# mptt-controller.net
KiCad netlist of a schematic drawn in EAGLE
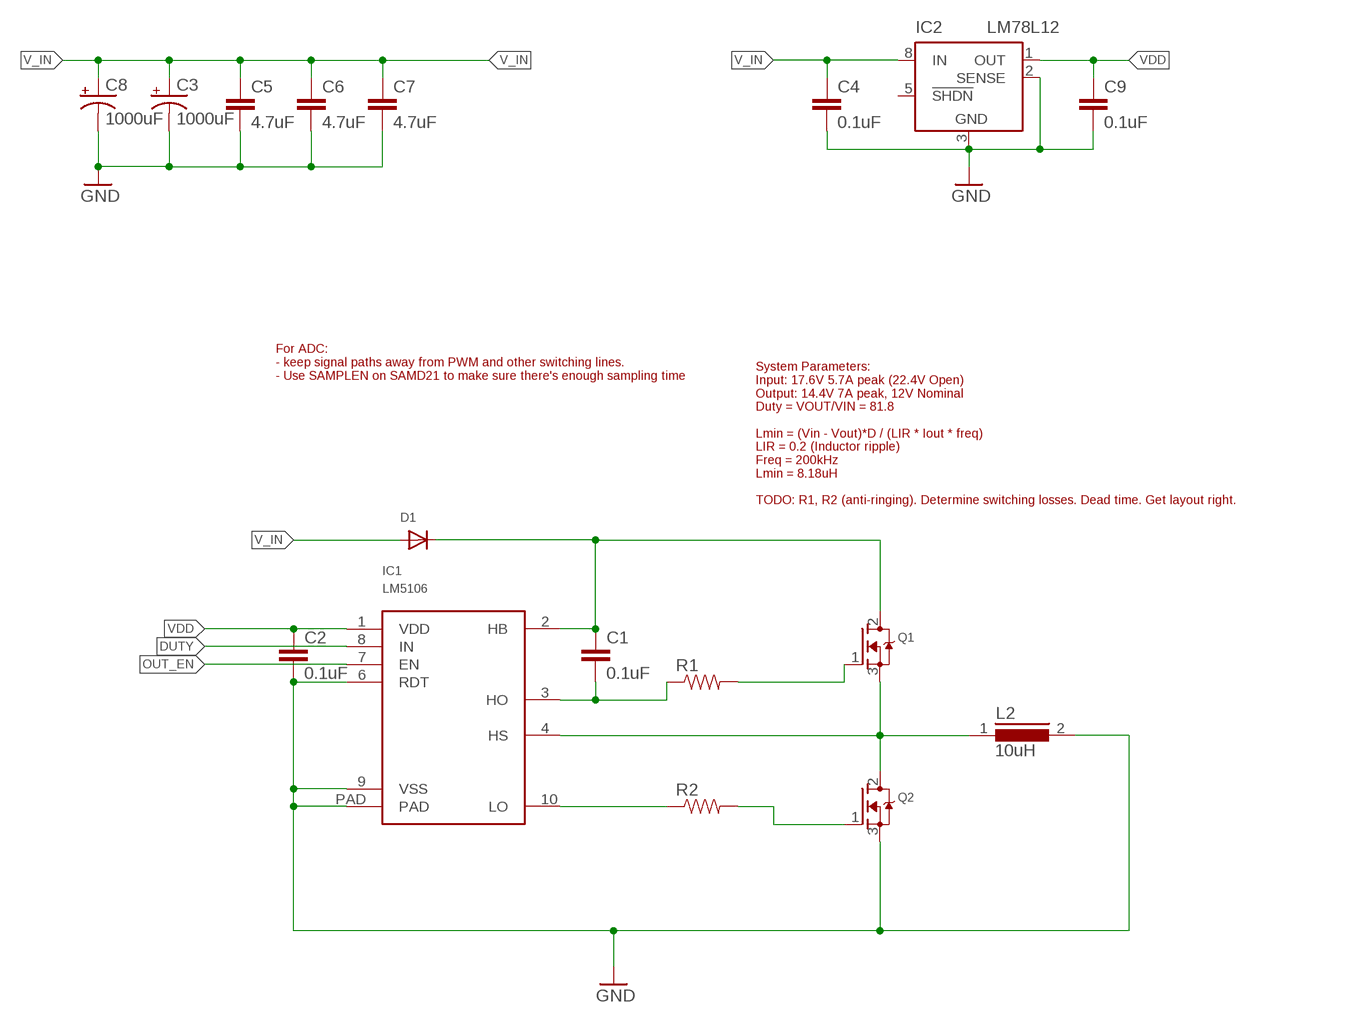
[diagram p0: schematic, sheet 1]

(export (version "E")
  (design (tool "Eeschema 10.0.6"))
  (components
    (comp (ref "C1")
      (value "0.1uF")
      (footprint "eagle-import:0603-CAP")
      (libsource (lib "eagle-import") (part "0.1UF-25V(+80/-20%)(0603)"))
    )
    (comp (ref "C2")
      (value "0.1uF")
      (footprint "eagle-import:0603-CAP")
      (libsource (lib "eagle-import") (part "0.1UF-25V(+80/-20%)(0603)"))
    )
    (comp (ref "C3")
      (value "1000uF")
      (footprint "eagle-import:CPOL-RADIAL-1000UF-25V")
      (libsource (lib "eagle-import") (part "CAP_POLPTH4"))
    )
    (comp (ref "C4")
      (value "0.1uF")
      (footprint "eagle-import:0603-CAP")
      (libsource (lib "eagle-import") (part "0.1UF-25V(+80/-20%)(0603)"))
    )
    (comp (ref "C5")
      (value "4.7uF")
      (footprint "eagle-import:0603-CAP")
      (libsource (lib "eagle-import") (part "0.1UF-25V(+80/-20%)(0603)"))
    )
    (comp (ref "C6")
      (value "4.7uF")
      (footprint "eagle-import:0603-CAP")
      (libsource (lib "eagle-import") (part "0.1UF-25V(+80/-20%)(0603)"))
    )
    (comp (ref "C7")
      (value "4.7uF")
      (footprint "eagle-import:0603-CAP")
      (libsource (lib "eagle-import") (part "0.1UF-25V(+80/-20%)(0603)"))
    )
    (comp (ref "C8")
      (value "1000uF")
      (footprint "eagle-import:CPOL-RADIAL-1000UF-25V")
      (libsource (lib "eagle-import") (part "CAP_POLPTH4"))
    )
    (comp (ref "C9")
      (value "0.1uF")
      (footprint "eagle-import:0603-CAP")
      (libsource (lib "eagle-import") (part "0.1UF-25V(+80/-20%)(0603)"))
    )
    (comp (ref "D1")
      (value "DIODE_SOD-123FL")
      (footprint "eagle-import:SOD-123FL")
      (libsource (lib "eagle-import") (part "DIODE_SOD-123FL"))
    )
    (comp (ref "IC1")
      (value "LM5106")
      (footprint "eagle-import:10WSON")
      (libsource (lib "eagle-import") (part "LM5106"))
    )
    (comp (ref "IC2")
      (value "LM78L12")
      (footprint "eagle-import:SOIC8")
      (fields (field (name "MPN") "LT1963ES8"))
      (libsource (lib "eagle-import") (part "LT1963ES8"))
    )
    (comp (ref "L2")
      (value "10uH")
      (footprint "eagle-import:SFT1040")
      (libsource (lib "eagle-import") (part "SFT1040"))
    )
    (comp (ref "Q1")
      (value "MOSFET-NGDS_TO220V")
      (footprint "eagle-import:TO220V")
      (libsource (lib "eagle-import") (part "MOSFET-NGDS_TO220V"))
    )
    (comp (ref "Q2")
      (value "MOSFET-NGDS_TO220V")
      (footprint "eagle-import:TO220V")
      (libsource (lib "eagle-import") (part "MOSFET-NGDS_TO220V"))
    )
    (comp (ref "R1")
      (value "RESISTOR0603")
      (footprint "eagle-import:0603-RES")
      (libsource (lib "eagle-import") (part "RESISTOR0603"))
    )
    (comp (ref "R2")
      (value "RESISTOR0603")
      (footprint "eagle-import:0603-RES")
      (libsource (lib "eagle-import") (part "RESISTOR0603"))
    )
  )
  (nets
    (net (code "1") (name "DUTY") (class "Default")
      (node (ref "IC1") (pin "8") (pinfunction "IN_8") (pintype "bidirectional"))
    )
    (net (code "2") (name "GND") (class "Default")
      (node (ref "C2") (pin "2") (pinfunction "2_2") (pintype "passive"))
      (node (ref "C3") (pin "-") (pinfunction "-_-") (pintype "passive"))
      (node (ref "C4") (pin "2") (pinfunction "2_2") (pintype "passive"))
      (node (ref "C5") (pin "2") (pinfunction "2_2") (pintype "passive"))
      (node (ref "C6") (pin "2") (pinfunction "2_2") (pintype "passive"))
      (node (ref "C7") (pin "2") (pinfunction "2_2") (pintype "passive"))
      (node (ref "C8") (pin "-") (pinfunction "-_-") (pintype "passive"))
      (node (ref "C9") (pin "2") (pinfunction "2_2") (pintype "passive"))
      (node (ref "IC1") (pin "6") (pinfunction "RDT_6") (pintype "bidirectional"))
      (node (ref "IC1") (pin "9") (pinfunction "VSS_9") (pintype "bidirectional"))
      (node (ref "IC1") (pin "PAD") (pinfunction "PAD_PAD") (pintype "bidirectional"))
      (node (ref "IC2") (pin "2") (pinfunction "SENSE_2") (pintype "input"))
      (node (ref "IC2") (pin "3") (pinfunction "GND_3") (pintype "power_in"))
      (node (ref "L2") (pin "2") (pinfunction "2_2") (pintype "passive"))
      (node (ref "Q2") (pin "3") (pinfunction "S_3") (pintype "bidirectional"))
    )
    (net (code "3") (name "Net-(IC1-HB)") (class "Default")
      (node (ref "C1") (pin "1") (pinfunction "1_1") (pintype "passive"))
      (node (ref "D1") (pin "C") (pinfunction "C_C") (pintype "passive"))
      (node (ref "IC1") (pin "2") (pinfunction "HB_2") (pintype "bidirectional"))
      (node (ref "Q1") (pin "2") (pinfunction "D_2") (pintype "bidirectional"))
    )
    (net (code "4") (name "Net-(IC1-HO)") (class "Default")
      (node (ref "C1") (pin "2") (pinfunction "2_2") (pintype "passive"))
      (node (ref "IC1") (pin "3") (pinfunction "HO_3") (pintype "bidirectional"))
      (node (ref "R1") (pin "1") (pinfunction "1_1") (pintype "passive"))
    )
    (net (code "5") (name "Net-(IC1-HS)") (class "Default")
      (node (ref "IC1") (pin "4") (pinfunction "HS_4") (pintype "bidirectional"))
      (node (ref "L2") (pin "1") (pinfunction "1_1") (pintype "passive"))
      (node (ref "Q1") (pin "3") (pinfunction "S_3") (pintype "bidirectional"))
      (node (ref "Q2") (pin "2") (pinfunction "D_2") (pintype "bidirectional"))
    )
    (net (code "6") (name "Net-(IC1-LO)") (class "Default")
      (node (ref "IC1") (pin "10") (pinfunction "LO_10") (pintype "bidirectional"))
      (node (ref "R2") (pin "1") (pinfunction "1_1") (pintype "passive"))
    )
    (net (code "7") (name "Net-(Q1-G)") (class "Default")
      (node (ref "Q1") (pin "1") (pinfunction "G_1") (pintype "bidirectional"))
      (node (ref "R1") (pin "2") (pinfunction "2_2") (pintype "passive"))
    )
    (net (code "8") (name "Net-(Q2-G)") (class "Default")
      (node (ref "Q2") (pin "1") (pinfunction "G_1") (pintype "bidirectional"))
      (node (ref "R2") (pin "2") (pinfunction "2_2") (pintype "passive"))
    )
    (net (code "9") (name "OUT_EN") (class "Default")
      (node (ref "IC1") (pin "7") (pinfunction "EN_7") (pintype "bidirectional"))
    )
    (net (code "10") (name "VDD") (class "Default")
      (node (ref "C2") (pin "1") (pinfunction "1_1") (pintype "passive"))
      (node (ref "C9") (pin "1") (pinfunction "1_1") (pintype "passive"))
      (node (ref "IC1") (pin "1") (pinfunction "VDD_1") (pintype "bidirectional"))
      (node (ref "IC2") (pin "1") (pinfunction "OUT_1") (pintype "output"))
    )
    (net (code "11") (name "V_IN") (class "Default")
      (node (ref "C3") (pin "+") (pinfunction "+_+") (pintype "passive"))
      (node (ref "C4") (pin "1") (pinfunction "1_1") (pintype "passive"))
      (node (ref "C5") (pin "1") (pinfunction "1_1") (pintype "passive"))
      (node (ref "C6") (pin "1") (pinfunction "1_1") (pintype "passive"))
      (node (ref "C7") (pin "1") (pinfunction "1_1") (pintype "passive"))
      (node (ref "C8") (pin "+") (pinfunction "+_+") (pintype "passive"))
      (node (ref "D1") (pin "A") (pinfunction "A_A") (pintype "passive"))
      (node (ref "IC2") (pin "8") (pinfunction "IN_8") (pintype "input"))
    )
    (net (code "12") (name "unconnected-(IC2A-~{SHDN}-Pad5)") (class "Default")
      (node (ref "IC2") (pin "5") (pinfunction "~{SHDN}_5") (pintype "input"))
    )
  )
)
